# e80m.net
KiCad netlist of a schematic drawn in Altium Designer
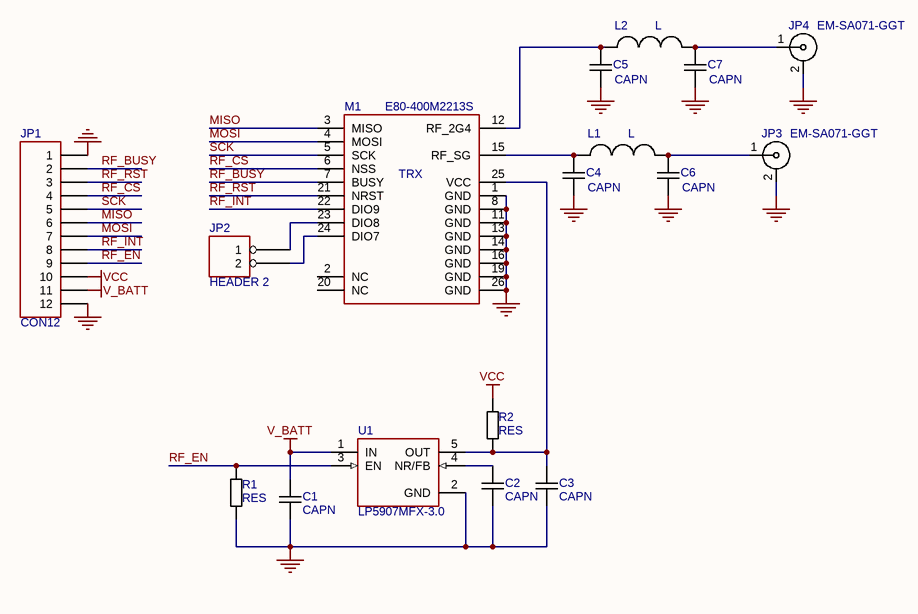
[diagram p0: e80m.SchDoc]

(export (version "E")
  (design (tool "Eeschema 10.0.6"))
  (components
    (comp (ref "C1")
      (value "CAPN")
      (footprint "C-0805")
      (fields (field (name "VOLTAGE") "50V"))
      (libsource (lib "Passive") (part "CAPN"))
    )
    (comp (ref "C2")
      (value "CAPN")
      (footprint "C-0603")
      (fields (field (name "VOLTAGE") "50V"))
      (libsource (lib "Passive") (part "CAPN"))
    )
    (comp (ref "C3")
      (value "CAPN")
      (footprint "C-0805")
      (fields (field (name "VOLTAGE") "50V"))
      (libsource (lib "Passive") (part "CAPN"))
    )
    (comp (ref "C4")
      (value "CAPN")
      (footprint "C-0603")
      (fields (field (name "VOLTAGE") "50V"))
      (libsource (lib "Passive") (part "CAPN"))
    )
    (comp (ref "C5")
      (value "CAPN")
      (footprint "C-0603")
      (fields (field (name "VOLTAGE") "50V"))
      (libsource (lib "Passive") (part "CAPN"))
    )
    (comp (ref "C6")
      (value "CAPN")
      (footprint "C-0603")
      (fields (field (name "VOLTAGE") "50V"))
      (libsource (lib "Passive") (part "CAPN"))
    )
    (comp (ref "C7")
      (value "CAPN")
      (footprint "C-0603")
      (fields (field (name "VOLTAGE") "50V"))
      (libsource (lib "Passive") (part "CAPN"))
    )
    (comp (ref "JP1")
      (value "CON12")
      (footprint "PBS1-12R")
      (description "Connector")
      (libsource (lib "Connectors") (part "CON12"))
    )
    (comp (ref "JP2")
      (value "HEADER 2")
      (footprint "PLS1-2")
      (libsource (lib "Connectors") (part "HEADER 2"))
    )
    (comp (ref "JP3")
      (value "EM-SA071-GGT")
      (footprint "SMA_F_EDGE")
      (description "SMA Female R/A PCB Mount")
      (libsource (lib "Connectors") (part "SMA"))
    )
    (comp (ref "JP4")
      (value "EM-SA071-GGT")
      (footprint "SMA_F_EDGE")
      (description "SMA Female R/A PCB Mount")
      (libsource (lib "Connectors") (part "SMA"))
    )
    (comp (ref "L1") (value "L") (footprint "L-0603") (libsource (lib "Passive") (part "L")))
    (comp (ref "L2") (value "L") (footprint "L-0603") (libsource (lib "Passive") (part "L")))
    (comp (ref "M1") (value "E80-400M2213S") (footprint "E80") (libsource (lib "RFmodules") (part "E80")))
    (comp (ref "R1") (value "RES") (footprint "R-0603") (libsource (lib "Passive") (part "RES")))
    (comp (ref "R2") (value "RES") (footprint "R-0603") (libsource (lib "Passive") (part "RES")))
    (comp (ref "U1")
      (value "LP5907MFX-3.0")
      (footprint "SOT-23-5")
      (description "250mA Low-Dropout Regulator")
      (libsource (lib "ICs") (part "LP5907"))
    )
  )
  (nets
    (net (code "1") (name "/MISO") (class "Default")
      (node (ref "JP1") (pin "6") (pinfunction "6_6") (pintype "passive"))
      (node (ref "M1") (pin "3") (pinfunction "MISO_3") (pintype "passive"))
    )
    (net (code "2") (name "/MOSI") (class "Default")
      (node (ref "JP1") (pin "7") (pinfunction "7_7") (pintype "passive"))
      (node (ref "M1") (pin "4") (pinfunction "MOSI_4") (pintype "passive"))
    )
    (net (code "3") (name "/RF_BUSY") (class "Default")
      (node (ref "JP1") (pin "2") (pinfunction "2_2") (pintype "passive"))
      (node (ref "M1") (pin "7") (pinfunction "BUSY_7") (pintype "passive"))
    )
    (net (code "4") (name "/RF_CS") (class "Default")
      (node (ref "JP1") (pin "4") (pinfunction "4_4") (pintype "passive"))
      (node (ref "M1") (pin "6") (pinfunction "NSS_6") (pintype "passive"))
    )
    (net (code "5") (name "/RF_EN") (class "Default")
      (node (ref "JP1") (pin "9") (pinfunction "9_9") (pintype "passive"))
      (node (ref "R1") (pin "2") (pinfunction "2_2") (pintype "passive"))
      (node (ref "U1") (pin "3") (pinfunction "EN_3") (pintype "input"))
    )
    (net (code "6") (name "/RF_INT") (class "Default")
      (node (ref "JP1") (pin "8") (pinfunction "8_8") (pintype "passive"))
      (node (ref "M1") (pin "22") (pinfunction "DIO9_22") (pintype "passive"))
    )
    (net (code "7") (name "/RF_RST") (class "Default")
      (node (ref "JP1") (pin "3") (pinfunction "3_3") (pintype "passive"))
      (node (ref "M1") (pin "21") (pinfunction "NRST_21") (pintype "passive"))
    )
    (net (code "8") (name "/SCK") (class "Default")
      (node (ref "JP1") (pin "5") (pinfunction "5_5") (pintype "passive"))
      (node (ref "M1") (pin "5") (pinfunction "SCK_5") (pintype "passive"))
    )
    (net (code "9") (name "GND") (class "Default")
      (node (ref "C1") (pin "2") (pinfunction "2_2") (pintype "passive"))
      (node (ref "C2") (pin "2") (pinfunction "2_2") (pintype "passive"))
      (node (ref "C3") (pin "2") (pinfunction "2_2") (pintype "passive"))
      (node (ref "C4") (pin "2") (pinfunction "2_2") (pintype "passive"))
      (node (ref "C5") (pin "2") (pinfunction "2_2") (pintype "passive"))
      (node (ref "C6") (pin "2") (pinfunction "2_2") (pintype "passive"))
      (node (ref "C7") (pin "2") (pinfunction "2_2") (pintype "passive"))
      (node (ref "JP1") (pin "1") (pinfunction "1_1") (pintype "passive"))
      (node (ref "JP1") (pin "12") (pinfunction "12_12") (pintype "passive"))
      (node (ref "JP3") (pin "2") (pinfunction "2_2") (pintype "passive"))
      (node (ref "JP4") (pin "2") (pinfunction "2_2") (pintype "passive"))
      (node (ref "M1") (pin "1") (pinfunction "GND_1") (pintype "passive"))
      (node (ref "M1") (pin "11") (pinfunction "GND_11") (pintype "passive"))
      (node (ref "M1") (pin "13") (pinfunction "GND_13") (pintype "passive"))
      (node (ref "M1") (pin "14") (pinfunction "GND_14") (pintype "passive"))
      (node (ref "M1") (pin "16") (pinfunction "GND_16") (pintype "passive"))
      (node (ref "M1") (pin "19") (pinfunction "GND_19") (pintype "passive"))
      (node (ref "M1") (pin "26") (pinfunction "GND_26") (pintype "passive"))
      (node (ref "M1") (pin "8") (pinfunction "GND_8") (pintype "passive"))
      (node (ref "R1") (pin "1") (pinfunction "1_1") (pintype "passive"))
      (node (ref "U1") (pin "2") (pinfunction "GND_2") (pintype "power_in"))
    )
    (net (code "10") (name "Net-(C6-Pad1)") (class "Default")
      (node (ref "C6") (pin "1") (pinfunction "1_1") (pintype "passive"))
      (node (ref "JP3") (pin "1") (pinfunction "1_1") (pintype "passive"))
      (node (ref "L1") (pin "2") (pinfunction "2_2") (pintype "passive"))
    )
    (net (code "11") (name "Net-(C7-Pad1)") (class "Default")
      (node (ref "C7") (pin "1") (pinfunction "1_1") (pintype "passive"))
      (node (ref "JP4") (pin "1") (pinfunction "1_1") (pintype "passive"))
      (node (ref "L2") (pin "2") (pinfunction "2_2") (pintype "passive"))
    )
    (net (code "12") (name "Net-(M1-DIO7)") (class "Default")
      (node (ref "JP2") (pin "2") (pinfunction "2_2") (pintype "passive"))
      (node (ref "M1") (pin "24") (pinfunction "DIO7_24") (pintype "passive"))
    )
    (net (code "13") (name "Net-(M1-DIO8)") (class "Default")
      (node (ref "JP2") (pin "1") (pinfunction "1_1") (pintype "passive"))
      (node (ref "M1") (pin "23") (pinfunction "DIO8_23") (pintype "passive"))
    )
    (net (code "14") (name "Net-(M1-RF_2G4)") (class "Default")
      (node (ref "C5") (pin "1") (pinfunction "1_1") (pintype "passive"))
      (node (ref "L2") (pin "1") (pinfunction "1_1") (pintype "passive"))
      (node (ref "M1") (pin "12") (pinfunction "RF_2G4_12") (pintype "passive"))
    )
    (net (code "15") (name "Net-(M1-RF_SG)") (class "Default")
      (node (ref "C4") (pin "1") (pinfunction "1_1") (pintype "passive"))
      (node (ref "L1") (pin "1") (pinfunction "1_1") (pintype "passive"))
      (node (ref "M1") (pin "15") (pinfunction "RF_SG_15") (pintype "passive"))
    )
    (net (code "16") (name "Net-(M1-VCC)") (class "Default")
      (node (ref "C3") (pin "1") (pinfunction "1_1") (pintype "passive"))
      (node (ref "M1") (pin "25") (pinfunction "VCC_25") (pintype "passive"))
      (node (ref "R2") (pin "1") (pinfunction "1_1") (pintype "passive"))
      (node (ref "U1") (pin "5") (pinfunction "OUT_5") (pintype "power_in"))
    )
    (net (code "17") (name "Net-(U1-NR{slash}FB)") (class "Default")
      (node (ref "C2") (pin "1") (pinfunction "1_1") (pintype "passive"))
      (node (ref "U1") (pin "4") (pinfunction "NR/FB_4") (pintype "input"))
    )
    (net (code "18") (name "VCC") (class "Default")
      (node (ref "JP1") (pin "10") (pinfunction "10_10") (pintype "passive"))
      (node (ref "R2") (pin "2") (pinfunction "2_2") (pintype "passive"))
    )
    (net (code "19") (name "V_BATT") (class "Default")
      (node (ref "C1") (pin "1") (pinfunction "1_1") (pintype "passive"))
      (node (ref "JP1") (pin "11") (pinfunction "11_11") (pintype "passive"))
      (node (ref "U1") (pin "1") (pinfunction "IN_1") (pintype "power_in"))
    )
    (net (code "20") (name "unconnected-(M1-NC-Pad2)") (class "Default")
      (node (ref "M1") (pin "2") (pinfunction "NC_2") (pintype "passive"))
    )
    (net (code "21") (name "unconnected-(M1-NC-Pad20)") (class "Default")
      (node (ref "M1") (pin "20") (pinfunction "NC_20") (pintype "passive"))
    )
  )
)
